# ULN2003.net
KiCad netlist of a schematic drawn in Altium Designer
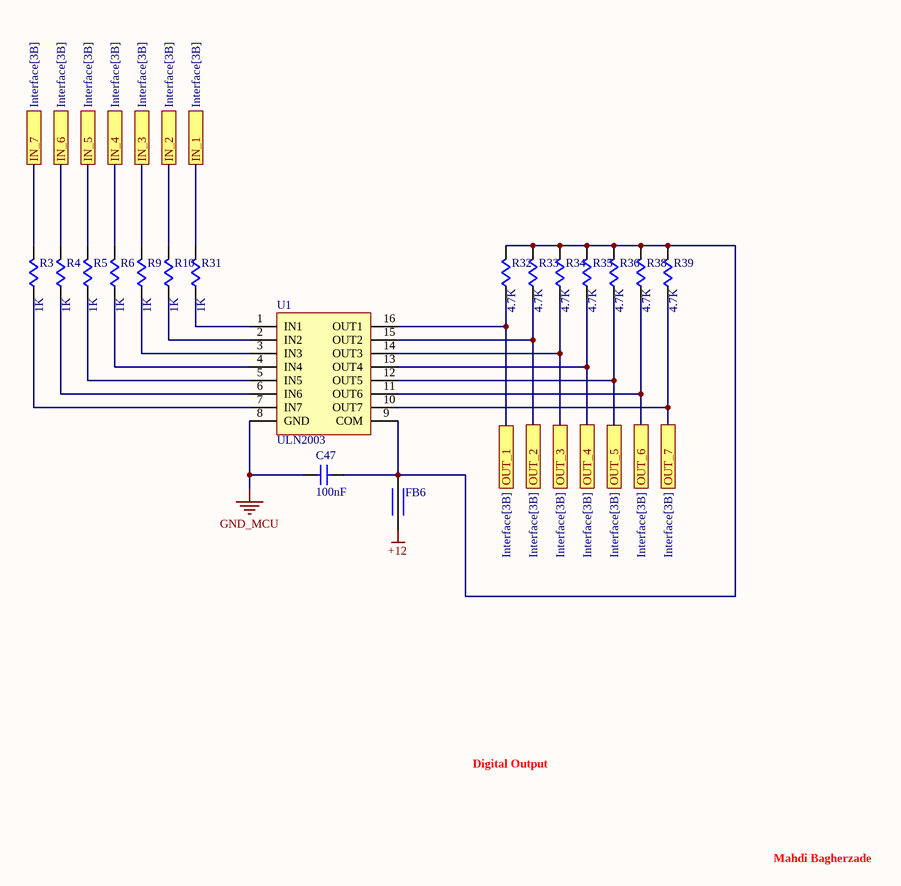
[diagram p0: ULN2003.SchDoc]

(export (version "E")
  (design (tool "Eeschema 10.0.6"))
  (components
    (comp (ref "C47")
      (value "100nF")
      (footprint "C-0805")
      (description "CAPACITOR")
      (fields
        (field (name "VOLTAGE") "50V")
        (field (name "TOLERANCE") "X7R")
        (field (name "PUBLISHER") "Mahdi Bagherzadeh")
      )
      (libsource (lib "Mahdi-Bagherzadeh") (part "CAP-CER"))
    )
    (comp (ref "FB6")
      (value "Ferrite Bead SMD")
      (footprint "FB-0805")
      (description "INDUCATOR")
      (fields (field (name "PUBLISHER") "Mahdi Bagherzadeh"))
      (libsource (lib "Mahdi-Bagherzadeh") (part "FERRITE BEAD"))
    )
    (comp (ref "R3")
      (value "1K")
      (footprint "R-0805")
      (description "RESISTOR")
      (fields
        (field (name "POWER") "1/8W")
        (field (name "TOLERANCE") "5%")
        (field (name "PUBLISHER") "Mahdi Bagherzadeh")
      )
      (libsource (lib "Mahdi-Bagherzadeh") (part "RES"))
    )
    (comp (ref "R4")
      (value "1K")
      (footprint "R-0805")
      (description "RESISTOR")
      (fields
        (field (name "POWER") "1/8W")
        (field (name "TOLERANCE") "5%")
        (field (name "PUBLISHER") "Mahdi Bagherzadeh")
      )
      (libsource (lib "Mahdi-Bagherzadeh") (part "RES"))
    )
    (comp (ref "R5")
      (value "1K")
      (footprint "R-0805")
      (description "RESISTOR")
      (fields
        (field (name "POWER") "1/8W")
        (field (name "TOLERANCE") "5%")
        (field (name "PUBLISHER") "Mahdi Bagherzadeh")
      )
      (libsource (lib "Mahdi-Bagherzadeh") (part "RES"))
    )
    (comp (ref "R6")
      (value "1K")
      (footprint "R-0805")
      (description "RESISTOR")
      (fields
        (field (name "POWER") "1/8W")
        (field (name "TOLERANCE") "5%")
        (field (name "PUBLISHER") "Mahdi Bagherzadeh")
      )
      (libsource (lib "Mahdi-Bagherzadeh") (part "RES"))
    )
    (comp (ref "R9")
      (value "1K")
      (footprint "R-0805")
      (description "RESISTOR")
      (fields
        (field (name "POWER") "1/8W")
        (field (name "TOLERANCE") "5%")
        (field (name "PUBLISHER") "Mahdi Bagherzadeh")
      )
      (libsource (lib "Mahdi-Bagherzadeh") (part "RES"))
    )
    (comp (ref "R10")
      (value "1K")
      (footprint "R-0805")
      (description "RESISTOR")
      (fields
        (field (name "POWER") "1/8W")
        (field (name "TOLERANCE") "5%")
        (field (name "PUBLISHER") "Mahdi Bagherzadeh")
      )
      (libsource (lib "Mahdi-Bagherzadeh") (part "RES"))
    )
    (comp (ref "R31")
      (value "1K")
      (footprint "R-0805")
      (description "RESISTOR")
      (fields
        (field (name "POWER") "1/8W")
        (field (name "TOLERANCE") "5%")
        (field (name "PUBLISHER") "Mahdi Bagherzadeh")
      )
      (libsource (lib "Mahdi-Bagherzadeh") (part "RES"))
    )
    (comp (ref "R32")
      (value "4.7K")
      (footprint "R-0805")
      (description "RESISTOR")
      (fields
        (field (name "POWER") "1/8W")
        (field (name "TOLERANCE") "5%")
        (field (name "PUBLISHER") "Mahdi Bagherzadeh")
      )
      (libsource (lib "Mahdi-Bagherzadeh") (part "RES"))
    )
    (comp (ref "R33")
      (value "4.7K")
      (footprint "R-0805")
      (description "RESISTOR")
      (fields
        (field (name "POWER") "1/8W")
        (field (name "TOLERANCE") "5%")
        (field (name "PUBLISHER") "Mahdi Bagherzadeh")
      )
      (libsource (lib "Mahdi-Bagherzadeh") (part "RES"))
    )
    (comp (ref "R34")
      (value "4.7K")
      (footprint "R-0805")
      (description "RESISTOR")
      (fields
        (field (name "POWER") "1/8W")
        (field (name "TOLERANCE") "5%")
        (field (name "PUBLISHER") "Mahdi Bagherzadeh")
      )
      (libsource (lib "Mahdi-Bagherzadeh") (part "RES"))
    )
    (comp (ref "R35")
      (value "4.7K")
      (footprint "R-0805")
      (description "RESISTOR")
      (fields
        (field (name "POWER") "1/8W")
        (field (name "TOLERANCE") "5%")
        (field (name "PUBLISHER") "Mahdi Bagherzadeh")
      )
      (libsource (lib "Mahdi-Bagherzadeh") (part "RES"))
    )
    (comp (ref "R36")
      (value "4.7K")
      (footprint "R-0805")
      (description "RESISTOR")
      (fields
        (field (name "POWER") "1/8W")
        (field (name "TOLERANCE") "5%")
        (field (name "PUBLISHER") "Mahdi Bagherzadeh")
      )
      (libsource (lib "Mahdi-Bagherzadeh") (part "RES"))
    )
    (comp (ref "R38")
      (value "4.7K")
      (footprint "R-0805")
      (description "RESISTOR")
      (fields
        (field (name "POWER") "1/8W")
        (field (name "TOLERANCE") "5%")
        (field (name "PUBLISHER") "Mahdi Bagherzadeh")
      )
      (libsource (lib "Mahdi-Bagherzadeh") (part "RES"))
    )
    (comp (ref "R39")
      (value "4.7K")
      (footprint "R-0805")
      (description "RESISTOR")
      (fields
        (field (name "POWER") "1/8W")
        (field (name "TOLERANCE") "5%")
        (field (name "PUBLISHER") "Mahdi Bagherzadeh")
      )
      (libsource (lib "Mahdi-Bagherzadeh") (part "RES"))
    )
    (comp (ref "U1")
      (value "ULN2003")
      (footprint "SOIC16")
      (description "IC")
      (fields (field (name "PUBLISHER") "Mahdi Bagherzadeh"))
      (libsource (lib "Mahdi-Bagherzadeh") (part "ULN2003"))
    )
  )
  (nets
    (net (code "1") (name "+12") (class "Default")
      (node (ref "FB6") (pin "1") (pinfunction "1_1") (pintype "passive"))
    )
    (net (code "2") (name "/IN_1") (class "Default")
      (node (ref "R31") (pin "2") (pinfunction "2_2") (pintype "passive"))
    )
    (net (code "3") (name "/IN_2") (class "Default")
      (node (ref "R10") (pin "2") (pinfunction "2_2") (pintype "passive"))
    )
    (net (code "4") (name "/IN_3") (class "Default")
      (node (ref "R9") (pin "2") (pinfunction "2_2") (pintype "passive"))
    )
    (net (code "5") (name "/IN_4") (class "Default")
      (node (ref "R6") (pin "2") (pinfunction "2_2") (pintype "passive"))
    )
    (net (code "6") (name "/IN_5") (class "Default")
      (node (ref "R5") (pin "2") (pinfunction "2_2") (pintype "passive"))
    )
    (net (code "7") (name "/IN_6") (class "Default")
      (node (ref "R4") (pin "2") (pinfunction "2_2") (pintype "passive"))
    )
    (net (code "8") (name "/IN_7") (class "Default")
      (node (ref "R3") (pin "2") (pinfunction "2_2") (pintype "passive"))
    )
    (net (code "9") (name "/OUT_1") (class "Default")
      (node (ref "R32") (pin "1") (pinfunction "1_1") (pintype "passive"))
      (node (ref "U1") (pin "16") (pinfunction "OUT1_16") (pintype "passive"))
    )
    (net (code "10") (name "/OUT_2") (class "Default")
      (node (ref "R33") (pin "1") (pinfunction "1_1") (pintype "passive"))
      (node (ref "U1") (pin "15") (pinfunction "OUT2_15") (pintype "passive"))
    )
    (net (code "11") (name "/OUT_3") (class "Default")
      (node (ref "R34") (pin "1") (pinfunction "1_1") (pintype "passive"))
      (node (ref "U1") (pin "14") (pinfunction "OUT3_14") (pintype "passive"))
    )
    (net (code "12") (name "/OUT_4") (class "Default")
      (node (ref "R35") (pin "1") (pinfunction "1_1") (pintype "passive"))
      (node (ref "U1") (pin "13") (pinfunction "OUT4_13") (pintype "passive"))
    )
    (net (code "13") (name "/OUT_5") (class "Default")
      (node (ref "R36") (pin "1") (pinfunction "1_1") (pintype "passive"))
      (node (ref "U1") (pin "12") (pinfunction "OUT5_12") (pintype "passive"))
    )
    (net (code "14") (name "/OUT_6") (class "Default")
      (node (ref "R38") (pin "1") (pinfunction "1_1") (pintype "passive"))
      (node (ref "U1") (pin "11") (pinfunction "OUT6_11") (pintype "passive"))
    )
    (net (code "15") (name "/OUT_7") (class "Default")
      (node (ref "R39") (pin "1") (pinfunction "1_1") (pintype "passive"))
      (node (ref "U1") (pin "10") (pinfunction "OUT7_10") (pintype "passive"))
    )
    (net (code "16") (name "GND_MCU") (class "Default")
      (node (ref "C47") (pin "1") (pinfunction "1_1") (pintype "passive"))
      (node (ref "U1") (pin "8") (pinfunction "GND_8") (pintype "passive"))
    )
    (net (code "17") (name "Net-(U1-COM)") (class "Default")
      (node (ref "C47") (pin "2") (pinfunction "2_2") (pintype "passive"))
      (node (ref "FB6") (pin "2") (pinfunction "2_2") (pintype "passive"))
      (node (ref "R32") (pin "2") (pinfunction "2_2") (pintype "passive"))
      (node (ref "R33") (pin "2") (pinfunction "2_2") (pintype "passive"))
      (node (ref "R34") (pin "2") (pinfunction "2_2") (pintype "passive"))
      (node (ref "R35") (pin "2") (pinfunction "2_2") (pintype "passive"))
      (node (ref "R36") (pin "2") (pinfunction "2_2") (pintype "passive"))
      (node (ref "R38") (pin "2") (pinfunction "2_2") (pintype "passive"))
      (node (ref "R39") (pin "2") (pinfunction "2_2") (pintype "passive"))
      (node (ref "U1") (pin "9") (pinfunction "COM_9") (pintype "passive"))
    )
    (net (code "18") (name "Net-(U1-IN1)") (class "Default")
      (node (ref "R31") (pin "1") (pinfunction "1_1") (pintype "passive"))
      (node (ref "U1") (pin "1") (pinfunction "IN1_1") (pintype "passive"))
    )
    (net (code "19") (name "Net-(U1-IN2)") (class "Default")
      (node (ref "R10") (pin "1") (pinfunction "1_1") (pintype "passive"))
      (node (ref "U1") (pin "2") (pinfunction "IN2_2") (pintype "passive"))
    )
    (net (code "20") (name "Net-(U1-IN3)") (class "Default")
      (node (ref "R9") (pin "1") (pinfunction "1_1") (pintype "passive"))
      (node (ref "U1") (pin "3") (pinfunction "IN3_3") (pintype "passive"))
    )
    (net (code "21") (name "Net-(U1-IN4)") (class "Default")
      (node (ref "R6") (pin "1") (pinfunction "1_1") (pintype "passive"))
      (node (ref "U1") (pin "4") (pinfunction "IN4_4") (pintype "passive"))
    )
    (net (code "22") (name "Net-(U1-IN5)") (class "Default")
      (node (ref "R5") (pin "1") (pinfunction "1_1") (pintype "passive"))
      (node (ref "U1") (pin "5") (pinfunction "IN5_5") (pintype "passive"))
    )
    (net (code "23") (name "Net-(U1-IN6)") (class "Default")
      (node (ref "R4") (pin "1") (pinfunction "1_1") (pintype "passive"))
      (node (ref "U1") (pin "6") (pinfunction "IN6_6") (pintype "passive"))
    )
    (net (code "24") (name "Net-(U1-IN7)") (class "Default")
      (node (ref "R3") (pin "1") (pinfunction "1_1") (pintype "passive"))
      (node (ref "U1") (pin "7") (pinfunction "IN7_7") (pintype "passive"))
    )
  )
)
